# USB_PROGRAMER.net
KiCad netlist of a schematic drawn in Altium Designer
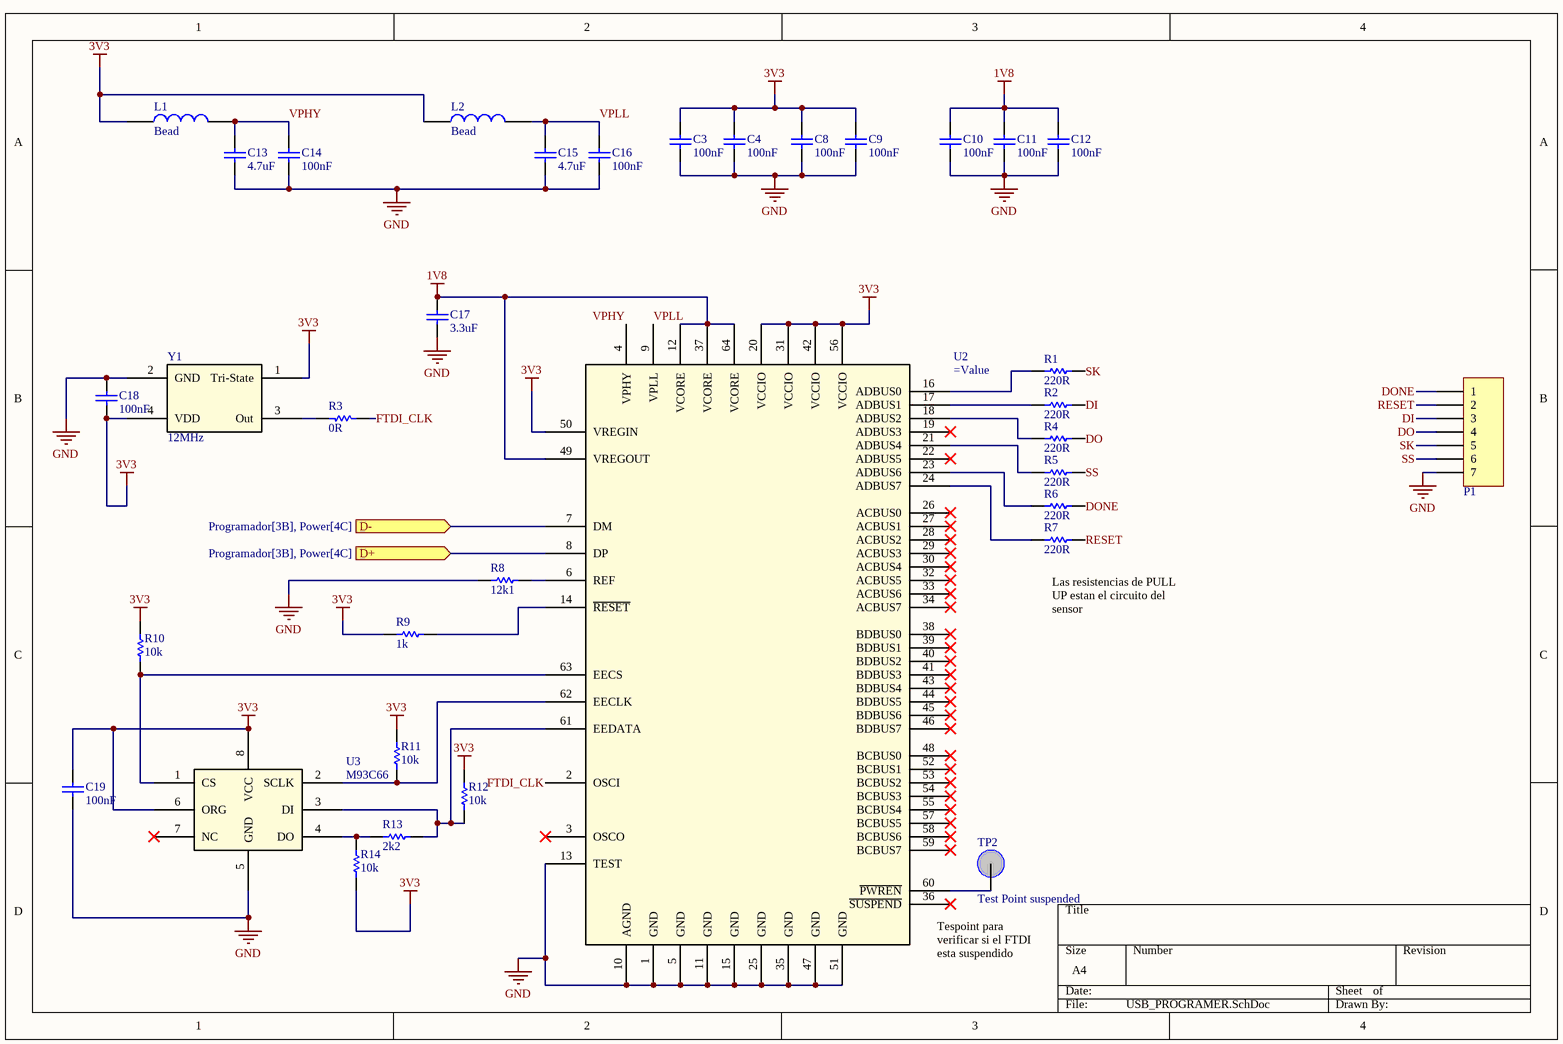
[diagram p0: USB_PROGRAMER.SchDoc]

(export (version "E")
  (design (tool "Eeschema 10.0.6"))
  (components
    (comp (ref "C3")
      (value "100nF")
      (footprint "C_0805_2013_b")
      (description "Capacitor SMD 0805")
      (fields (field (name "TOLERANCE") "10%") (field (name "VOLTAGE") "50V"))
      (libsource (lib "MyLibraryV2") (part "C_100nF_50V_b"))
    )
    (comp (ref "C4")
      (value "100nF")
      (footprint "C_0805_2013_b")
      (description "Capacitor SMD 0805")
      (fields (field (name "TOLERANCE") "10%") (field (name "VOLTAGE") "50V"))
      (libsource (lib "MyLibraryV2") (part "C_100nF_50V_b"))
    )
    (comp (ref "C8")
      (value "100nF")
      (footprint "C_0805_2013_b")
      (description "Capacitor SMD 0805")
      (fields (field (name "TOLERANCE") "10%") (field (name "VOLTAGE") "50V"))
      (libsource (lib "MyLibraryV2") (part "C_100nF_50V_b"))
    )
    (comp (ref "C9")
      (value "100nF")
      (footprint "C_0805_2013_b")
      (description "Capacitor SMD 0805")
      (fields (field (name "TOLERANCE") "10%") (field (name "VOLTAGE") "50V"))
      (libsource (lib "MyLibraryV2") (part "C_100nF_50V_b"))
    )
    (comp (ref "C10")
      (value "100nF")
      (footprint "C_0805_2013_b")
      (description "Capacitor SMD 0805")
      (fields (field (name "TOLERANCE") "10%") (field (name "VOLTAGE") "50V"))
      (libsource (lib "MyLibraryV2") (part "C_100nF_50V_b"))
    )
    (comp (ref "C11")
      (value "100nF")
      (footprint "C_0805_2013_b")
      (description "Capacitor SMD 0805")
      (fields (field (name "TOLERANCE") "10%") (field (name "VOLTAGE") "50V"))
      (libsource (lib "MyLibraryV2") (part "C_100nF_50V_b"))
    )
    (comp (ref "C12")
      (value "100nF")
      (footprint "C_0805_2013_b")
      (description "Capacitor SMD 0805")
      (fields (field (name "TOLERANCE") "10%") (field (name "VOLTAGE") "50V"))
      (libsource (lib "MyLibraryV2") (part "C_100nF_50V_b"))
    )
    (comp (ref "C13")
      (value "4.7uF")
      (footprint "C_0805_2013_b")
      (description "(Modificar) Capacitor SMD 0805")
      (libsource (lib "MyLibraryV2") (part "C_4.7uF_10V_b"))
    )
    (comp (ref "C14")
      (value "100nF")
      (footprint "C_0805_2013_b")
      (description "Capacitor SMD 0805")
      (fields (field (name "TOLERANCE") "10%") (field (name "VOLTAGE") "50V"))
      (libsource (lib "MyLibraryV2") (part "C_100nF_50V_b"))
    )
    (comp (ref "C15")
      (value "4.7uF")
      (footprint "C_0805_2013_b")
      (description "(Modificar) Capacitor SMD 0805")
      (libsource (lib "MyLibraryV2") (part "C_4.7uF_10V_b"))
    )
    (comp (ref "C16")
      (value "100nF")
      (footprint "C_0805_2013_b")
      (description "Capacitor SMD 0805")
      (fields (field (name "TOLERANCE") "10%") (field (name "VOLTAGE") "50V"))
      (libsource (lib "MyLibraryV2") (part "C_100nF_50V_b"))
    )
    (comp (ref "C17")
      (value "3.3uF")
      (footprint "C_0805_2013_b")
      (description "(Generico) Capacitor SMD 0805")
      (libsource (lib "MyLibraryV2") (part "C_?F_?_b"))
    )
    (comp (ref "C18")
      (value "100nF")
      (footprint "C_0805_2013_b")
      (description "Capacitor SMD 0805")
      (fields (field (name "TOLERANCE") "10%") (field (name "VOLTAGE") "50V"))
      (libsource (lib "MyLibraryV2") (part "C_100nF_50V_b"))
    )
    (comp (ref "C19")
      (value "100nF")
      (footprint "C_0805_2013_b")
      (description "Capacitor SMD 0805")
      (fields (field (name "TOLERANCE") "10%") (field (name "VOLTAGE") "50V"))
      (libsource (lib "MyLibraryV2") (part "C_100nF_50V_b"))
    )
    (comp (ref "L1")
      (value "Bead")
      (footprint "L_0805_2013")
      (description "Inductor SMD 0805")
      (fields
        (field (name "MANUFACTURER") "Pulse")
        (field (name "MANUFACTURER PART NUMBER") "PE-0805PFB600ST")
      )
      (libsource (lib "MyLibraryV2") (part "L_Bead"))
    )
    (comp (ref "L2")
      (value "Bead")
      (footprint "L_0805_2013")
      (description "Inductor SMD 0805")
      (fields
        (field (name "MANUFACTURER") "Pulse")
        (field (name "MANUFACTURER PART NUMBER") "PE-0805PFB600ST")
      )
      (libsource (lib "MyLibraryV2") (part "L_Bead"))
    )
    (comp (ref "P1")
      (value "BORNERA 6 ENCH")
      (footprint "P_CON1X7")
      (description "Bornera 7")
      (libsource (lib "MyLibraryV2") (part "P_BORNERA 7"))
    )
    (comp (ref "R1")
      (value "220R")
      (footprint "R_0805_2012_a")
      (description "Resistor SMD 0805")
      (fields (field (name "TOLERANCE") "1%") (field (name "MANUFACTURER") "Bourns"))
      (libsource (lib "MyLibraryV2") (part "R_220R_b"))
    )
    (comp (ref "R2")
      (value "220R")
      (footprint "R_0805_2012_a")
      (description "Resistor SMD 0805")
      (fields (field (name "TOLERANCE") "1%") (field (name "MANUFACTURER") "Bourns"))
      (libsource (lib "MyLibraryV2") (part "R_220R_b"))
    )
    (comp (ref "R3")
      (value "0R")
      (footprint "R_0805_2012_a")
      (description "Resistor SMD 0805")
      (fields
        (field (name "MANUFACTURER") "Stackpole Electronics")
        (field (name "MANUFACTURER PART NUMBER") "RMCF0805ZT0R00")
      )
      (libsource (lib "MyLibraryV2") (part "R_0R_b"))
    )
    (comp (ref "R4")
      (value "220R")
      (footprint "R_0805_2012_a")
      (description "Resistor SMD 0805")
      (fields (field (name "TOLERANCE") "1%") (field (name "MANUFACTURER") "Bourns"))
      (libsource (lib "MyLibraryV2") (part "R_220R_b"))
    )
    (comp (ref "R5")
      (value "220R")
      (footprint "R_0805_2012_a")
      (description "Resistor SMD 0805")
      (fields (field (name "TOLERANCE") "1%") (field (name "MANUFACTURER") "Bourns"))
      (libsource (lib "MyLibraryV2") (part "R_220R_b"))
    )
    (comp (ref "R6")
      (value "220R")
      (footprint "R_0805_2012_a")
      (description "Resistor SMD 0805")
      (fields (field (name "TOLERANCE") "1%") (field (name "MANUFACTURER") "Bourns"))
      (libsource (lib "MyLibraryV2") (part "R_220R_b"))
    )
    (comp (ref "R7")
      (value "220R")
      (footprint "R_0805_2012_a")
      (description "Resistor SMD 0805")
      (fields (field (name "TOLERANCE") "1%") (field (name "MANUFACTURER") "Bourns"))
      (libsource (lib "MyLibraryV2") (part "R_220R_b"))
    )
    (comp (ref "R8")
      (value "12k1")
      (footprint "R_0805_2012_a")
      (description "Resistor SMD 0805")
      (fields (field (name "TOLERANCE") "1%") (field (name "MANUFACTURER") "Stackpole Electronics"))
      (libsource (lib "MyLibraryV2") (part "R_12k1_b"))
    )
    (comp (ref "R9")
      (value "1k")
      (footprint "R_0805_2012_a")
      (description "Resistor SMD 0805")
      (fields (field (name "TOLERANCE") "1%") (field (name "MANUFACTURER") "Bourns"))
      (libsource (lib "MyLibraryV2") (part "R_1k_b"))
    )
    (comp (ref "R10")
      (value "10k")
      (footprint "R_0805_2012_a")
      (description "Resistor SMD 0805")
      (fields (field (name "TOLERANCE") "1%") (field (name "MANUFACTURER") "Yageo"))
      (libsource (lib "MyLibraryV2") (part "R_10k_b"))
    )
    (comp (ref "R11")
      (value "10k")
      (footprint "R_0805_2012_a")
      (description "Resistor SMD 0805")
      (fields (field (name "TOLERANCE") "1%") (field (name "MANUFACTURER") "Yageo"))
      (libsource (lib "MyLibraryV2") (part "R_10k_b"))
    )
    (comp (ref "R12")
      (value "10k")
      (footprint "R_0805_2012_a")
      (description "Resistor SMD 0805")
      (fields (field (name "TOLERANCE") "1%") (field (name "MANUFACTURER") "Yageo"))
      (libsource (lib "MyLibraryV2") (part "R_10k_b"))
    )
    (comp (ref "R13")
      (value "2k2")
      (footprint "R_0805_2012_a")
      (description "Resistor SMD 0805")
      (fields (field (name "TOLERANCE") "1%") (field (name "MANUFACTURER") "Bourns"))
      (libsource (lib "MyLibraryV2") (part "R_2k2_b"))
    )
    (comp (ref "R14")
      (value "10k")
      (footprint "R_0805_2012_a")
      (description "Resistor SMD 0805")
      (fields (field (name "TOLERANCE") "1%") (field (name "MANUFACTURER") "Yageo"))
      (libsource (lib "MyLibraryV2") (part "R_10k_b"))
    )
    (comp (ref "TP2")
      (value "Test Point suspended")
      (footprint "TP SMD")
      (description "Test Point SMD")
      (fields (field (name "PUBLISHER") "Altium Limited"))
      (libsource (lib "MyLibraryV2") (part "P_T_TP"))
    )
    (comp (ref "U2") (value "~") (footprint "U_TQFP-64") (libsource (lib "Mi_lib") (part "U_FT2232H")))
    (comp (ref "U3") (value "M93C66") (footprint "U_SO-8") (libsource (lib "Mi_lib") (part "U_M93C66")))
    (comp (ref "Y1")
      (value "12MHz")
      (footprint "Y_SMD-XTAL-12MHz")
      (libsource (lib "Mi_lib") (part "Y_12MHZ"))
    )
  )
  (nets
    (net (code "1") (name "/D+") (class "Default")
      (node (ref "U2") (pin "8") (pinfunction "DP_8") (pintype "passive"))
    )
    (net (code "2") (name "/D-") (class "Default")
      (node (ref "U2") (pin "7") (pinfunction "DM_7") (pintype "passive"))
    )
    (net (code "3") (name "/DI") (class "Default")
      (node (ref "P1") (pin "3") (pinfunction "3_3") (pintype "passive"))
      (node (ref "R2") (pin "2") (pinfunction "2_2") (pintype "passive"))
    )
    (net (code "4") (name "/DO") (class "Default")
      (node (ref "P1") (pin "4") (pinfunction "4_4") (pintype "passive"))
      (node (ref "R4") (pin "2") (pinfunction "2_2") (pintype "passive"))
    )
    (net (code "5") (name "/DONE") (class "Default")
      (node (ref "P1") (pin "1") (pinfunction "1_1") (pintype "passive"))
      (node (ref "R6") (pin "2") (pinfunction "2_2") (pintype "passive"))
    )
    (net (code "6") (name "/FTDI_CLK") (class "Default")
      (node (ref "R3") (pin "1") (pinfunction "1_1") (pintype "passive"))
      (node (ref "U2") (pin "2") (pinfunction "OSCI_2") (pintype "passive"))
    )
    (net (code "7") (name "/RESET") (class "Default")
      (node (ref "P1") (pin "2") (pinfunction "2_2") (pintype "passive"))
      (node (ref "R7") (pin "2") (pinfunction "2_2") (pintype "passive"))
    )
    (net (code "8") (name "/SK") (class "Default")
      (node (ref "P1") (pin "5") (pinfunction "5_5") (pintype "passive"))
      (node (ref "R1") (pin "2") (pinfunction "2_2") (pintype "passive"))
    )
    (net (code "9") (name "/SS") (class "Default")
      (node (ref "P1") (pin "6") (pinfunction "6_6") (pintype "passive"))
      (node (ref "R5") (pin "2") (pinfunction "2_2") (pintype "passive"))
    )
    (net (code "10") (name "/VPHY") (class "Default")
      (node (ref "C13") (pin "2") (pinfunction "2_2") (pintype "passive"))
      (node (ref "C14") (pin "2") (pinfunction "2_2") (pintype "passive"))
      (node (ref "L1") (pin "2") (pinfunction "2_2") (pintype "passive"))
      (node (ref "U2") (pin "4") (pinfunction "VPHY_4") (pintype "passive"))
    )
    (net (code "11") (name "/VPLL") (class "Default")
      (node (ref "C15") (pin "2") (pinfunction "2_2") (pintype "passive"))
      (node (ref "C16") (pin "2") (pinfunction "2_2") (pintype "passive"))
      (node (ref "L2") (pin "2") (pinfunction "2_2") (pintype "passive"))
      (node (ref "U2") (pin "9") (pinfunction "VPLL_9") (pintype "passive"))
    )
    (net (code "12") (name "1V8") (class "Default")
      (node (ref "C10") (pin "2") (pinfunction "2_2") (pintype "passive"))
      (node (ref "C11") (pin "2") (pinfunction "2_2") (pintype "passive"))
      (node (ref "C12") (pin "2") (pinfunction "2_2") (pintype "passive"))
      (node (ref "C17") (pin "2") (pinfunction "2_2") (pintype "passive"))
      (node (ref "U2") (pin "12") (pinfunction "VCORE_12") (pintype "passive"))
      (node (ref "U2") (pin "37") (pinfunction "VCORE_37") (pintype "passive"))
      (node (ref "U2") (pin "49") (pinfunction "VREGOUT_49") (pintype "passive"))
      (node (ref "U2") (pin "64") (pinfunction "VCORE_64") (pintype "passive"))
    )
    (net (code "13") (name "3V3") (class "Default")
      (node (ref "C18") (pin "1") (pinfunction "1_1") (pintype "passive"))
      (node (ref "C19") (pin "2") (pinfunction "2_2") (pintype "passive"))
      (node (ref "C3") (pin "2") (pinfunction "2_2") (pintype "passive"))
      (node (ref "C4") (pin "2") (pinfunction "2_2") (pintype "passive"))
      (node (ref "C8") (pin "2") (pinfunction "2_2") (pintype "passive"))
      (node (ref "C9") (pin "2") (pinfunction "2_2") (pintype "passive"))
      (node (ref "L1") (pin "1") (pinfunction "1_1") (pintype "passive"))
      (node (ref "L2") (pin "1") (pinfunction "1_1") (pintype "passive"))
      (node (ref "R10") (pin "2") (pinfunction "2_2") (pintype "passive"))
      (node (ref "R11") (pin "2") (pinfunction "2_2") (pintype "passive"))
      (node (ref "R12") (pin "2") (pinfunction "2_2") (pintype "passive"))
      (node (ref "R14") (pin "1") (pinfunction "1_1") (pintype "passive"))
      (node (ref "R9") (pin "1") (pinfunction "1_1") (pintype "passive"))
      (node (ref "U2") (pin "20") (pinfunction "VCCIO_20") (pintype "passive"))
      (node (ref "U2") (pin "31") (pinfunction "VCCIO_31") (pintype "passive"))
      (node (ref "U2") (pin "42") (pinfunction "VCCIO_42") (pintype "passive"))
      (node (ref "U2") (pin "50") (pinfunction "VREGIN_50") (pintype "passive"))
      (node (ref "U2") (pin "56") (pinfunction "VCCIO_56") (pintype "passive"))
      (node (ref "U3") (pin "6") (pinfunction "ORG_6") (pintype "passive"))
      (node (ref "U3") (pin "8") (pinfunction "VCC_8") (pintype "passive"))
      (node (ref "Y1") (pin "1") (pinfunction "Tri-State_1") (pintype "passive"))
      (node (ref "Y1") (pin "4") (pinfunction "VDD_4") (pintype "passive"))
    )
    (net (code "14") (name "GND") (class "Default")
      (node (ref "C10") (pin "1") (pinfunction "1_1") (pintype "passive"))
      (node (ref "C11") (pin "1") (pinfunction "1_1") (pintype "passive"))
      (node (ref "C12") (pin "1") (pinfunction "1_1") (pintype "passive"))
      (node (ref "C13") (pin "1") (pinfunction "1_1") (pintype "passive"))
      (node (ref "C14") (pin "1") (pinfunction "1_1") (pintype "passive"))
      (node (ref "C15") (pin "1") (pinfunction "1_1") (pintype "passive"))
      (node (ref "C16") (pin "1") (pinfunction "1_1") (pintype "passive"))
      (node (ref "C17") (pin "1") (pinfunction "1_1") (pintype "passive"))
      (node (ref "C18") (pin "2") (pinfunction "2_2") (pintype "passive"))
      (node (ref "C19") (pin "1") (pinfunction "1_1") (pintype "passive"))
      (node (ref "C3") (pin "1") (pinfunction "1_1") (pintype "passive"))
      (node (ref "C4") (pin "1") (pinfunction "1_1") (pintype "passive"))
      (node (ref "C8") (pin "1") (pinfunction "1_1") (pintype "passive"))
      (node (ref "C9") (pin "1") (pinfunction "1_1") (pintype "passive"))
      (node (ref "P1") (pin "7") (pinfunction "7_7") (pintype "passive"))
      (node (ref "R8") (pin "1") (pinfunction "1_1") (pintype "passive"))
      (node (ref "U2") (pin "1") (pinfunction "GND_1") (pintype "passive"))
      (node (ref "U2") (pin "10") (pinfunction "AGND_10") (pintype "passive"))
      (node (ref "U2") (pin "11") (pinfunction "GND_11") (pintype "passive"))
      (node (ref "U2") (pin "13") (pinfunction "TEST_13") (pintype "passive"))
      (node (ref "U2") (pin "15") (pinfunction "GND_15") (pintype "passive"))
      (node (ref "U2") (pin "25") (pinfunction "GND_25") (pintype "passive"))
      (node (ref "U2") (pin "35") (pinfunction "GND_35") (pintype "passive"))
      (node (ref "U2") (pin "47") (pinfunction "GND_47") (pintype "passive"))
      (node (ref "U2") (pin "5") (pinfunction "GND_5") (pintype "passive"))
      (node (ref "U2") (pin "51") (pinfunction "GND_51") (pintype "passive"))
      (node (ref "U3") (pin "5") (pinfunction "GND_5") (pintype "passive"))
      (node (ref "Y1") (pin "2") (pinfunction "GND_2") (pintype "passive"))
    )
    (net (code "15") (name "Net-(U2-ADBUS0)") (class "Default")
      (node (ref "R1") (pin "1") (pinfunction "1_1") (pintype "passive"))
      (node (ref "U2") (pin "16") (pinfunction "ADBUS0_16") (pintype "passive"))
    )
    (net (code "16") (name "Net-(U2-ADBUS1)") (class "Default")
      (node (ref "R2") (pin "1") (pinfunction "1_1") (pintype "passive"))
      (node (ref "U2") (pin "17") (pinfunction "ADBUS1_17") (pintype "passive"))
    )
    (net (code "17") (name "Net-(U2-ADBUS2)") (class "Default")
      (node (ref "R4") (pin "1") (pinfunction "1_1") (pintype "passive"))
      (node (ref "U2") (pin "18") (pinfunction "ADBUS2_18") (pintype "passive"))
    )
    (net (code "18") (name "Net-(U2-ADBUS4)") (class "Default")
      (node (ref "R5") (pin "1") (pinfunction "1_1") (pintype "passive"))
      (node (ref "U2") (pin "21") (pinfunction "ADBUS4_21") (pintype "passive"))
    )
    (net (code "19") (name "Net-(U2-ADBUS6)") (class "Default")
      (node (ref "R6") (pin "1") (pinfunction "1_1") (pintype "passive"))
      (node (ref "U2") (pin "23") (pinfunction "ADBUS6_23") (pintype "passive"))
    )
    (net (code "20") (name "Net-(U2-ADBUS7)") (class "Default")
      (node (ref "R7") (pin "1") (pinfunction "1_1") (pintype "passive"))
      (node (ref "U2") (pin "24") (pinfunction "ADBUS7_24") (pintype "passive"))
    )
    (net (code "21") (name "Net-(U2-EECLK)") (class "Default")
      (node (ref "R11") (pin "1") (pinfunction "1_1") (pintype "passive"))
      (node (ref "U2") (pin "62") (pinfunction "EECLK_62") (pintype "passive"))
      (node (ref "U3") (pin "2") (pinfunction "SCLK_2") (pintype "passive"))
    )
    (net (code "22") (name "Net-(U2-EECS)") (class "Default")
      (node (ref "R10") (pin "1") (pinfunction "1_1") (pintype "passive"))
      (node (ref "U2") (pin "63") (pinfunction "EECS_63") (pintype "passive"))
      (node (ref "U3") (pin "1") (pinfunction "CS_1") (pintype "passive"))
    )
    (net (code "23") (name "Net-(U2-EEDATA)") (class "Default")
      (node (ref "R12") (pin "1") (pinfunction "1_1") (pintype "passive"))
      (node (ref "R13") (pin "2") (pinfunction "2_2") (pintype "passive"))
      (node (ref "U2") (pin "61") (pinfunction "EEDATA_61") (pintype "passive"))
      (node (ref "U3") (pin "3") (pinfunction "DI_3") (pintype "passive"))
    )
    (net (code "24") (name "Net-(U2-REF)") (class "Default")
      (node (ref "R8") (pin "2") (pinfunction "2_2") (pintype "passive"))
      (node (ref "U2") (pin "6") (pinfunction "REF_6") (pintype "passive"))
    )
    (net (code "25") (name "Net-(U2-~{PWREN})") (class "Default")
      (node (ref "TP2") (pin "1") (pinfunction "1_1") (pintype "passive"))
      (node (ref "U2") (pin "60") (pinfunction "~{PWREN}_60") (pintype "passive"))
    )
    (net (code "26") (name "Net-(U2-~{RESET})") (class "Default")
      (node (ref "R9") (pin "2") (pinfunction "2_2") (pintype "passive"))
      (node (ref "U2") (pin "14") (pinfunction "~{RESET}_14") (pintype "passive"))
    )
    (net (code "27") (name "Net-(U3-DO)") (class "Default")
      (node (ref "R13") (pin "1") (pinfunction "1_1") (pintype "passive"))
      (node (ref "R14") (pin "2") (pinfunction "2_2") (pintype "passive"))
      (node (ref "U3") (pin "4") (pinfunction "DO_4") (pintype "passive"))
    )
    (net (code "28") (name "Net-(Y1-Out)") (class "Default")
      (node (ref "R3") (pin "2") (pinfunction "2_2") (pintype "passive"))
      (node (ref "Y1") (pin "3") (pinfunction "Out_3") (pintype "passive"))
    )
    (net (code "29") (name "unconnected-(U2-ACBUS0-Pad26)") (class "Default")
      (node (ref "U2") (pin "26") (pinfunction "ACBUS0_26") (pintype "passive+no_connect"))
    )
    (net (code "30") (name "unconnected-(U2-ACBUS1-Pad27)") (class "Default")
      (node (ref "U2") (pin "27") (pinfunction "ACBUS1_27") (pintype "passive+no_connect"))
    )
    (net (code "31") (name "unconnected-(U2-ACBUS2-Pad28)") (class "Default")
      (node (ref "U2") (pin "28") (pinfunction "ACBUS2_28") (pintype "passive+no_connect"))
    )
    (net (code "32") (name "unconnected-(U2-ACBUS3-Pad29)") (class "Default")
      (node (ref "U2") (pin "29") (pinfunction "ACBUS3_29") (pintype "passive+no_connect"))
    )
    (net (code "33") (name "unconnected-(U2-ACBUS4-Pad30)") (class "Default")
      (node (ref "U2") (pin "30") (pinfunction "ACBUS4_30") (pintype "passive+no_connect"))
    )
    (net (code "34") (name "unconnected-(U2-ACBUS5-Pad32)") (class "Default")
      (node (ref "U2") (pin "32") (pinfunction "ACBUS5_32") (pintype "passive+no_connect"))
    )
    (net (code "35") (name "unconnected-(U2-ACBUS6-Pad33)") (class "Default")
      (node (ref "U2") (pin "33") (pinfunction "ACBUS6_33") (pintype "passive+no_connect"))
    )
    (net (code "36") (name "unconnected-(U2-ACBUS7-Pad34)") (class "Default")
      (node (ref "U2") (pin "34") (pinfunction "ACBUS7_34") (pintype "passive+no_connect"))
    )
    (net (code "37") (name "unconnected-(U2-ADBUS3-Pad19)") (class "Default")
      (node (ref "U2") (pin "19") (pinfunction "ADBUS3_19") (pintype "passive+no_connect"))
    )
    (net (code "38") (name "unconnected-(U2-ADBUS5-Pad22)") (class "Default")
      (node (ref "U2") (pin "22") (pinfunction "ADBUS5_22") (pintype "passive+no_connect"))
    )
    (net (code "39") (name "unconnected-(U2-BCBUS0-Pad48)") (class "Default")
      (node (ref "U2") (pin "48") (pinfunction "BCBUS0_48") (pintype "passive+no_connect"))
    )
    (net (code "40") (name "unconnected-(U2-BCBUS1-Pad52)") (class "Default")
      (node (ref "U2") (pin "52") (pinfunction "BCBUS1_52") (pintype "passive+no_connect"))
    )
    (net (code "41") (name "unconnected-(U2-BCBUS2-Pad53)") (class "Default")
      (node (ref "U2") (pin "53") (pinfunction "BCBUS2_53") (pintype "passive+no_connect"))
    )
    (net (code "42") (name "unconnected-(U2-BCBUS3-Pad54)") (class "Default")
      (node (ref "U2") (pin "54") (pinfunction "BCBUS3_54") (pintype "passive+no_connect"))
    )
    (net (code "43") (name "unconnected-(U2-BCBUS4-Pad55)") (class "Default")
      (node (ref "U2") (pin "55") (pinfunction "BCBUS4_55") (pintype "passive+no_connect"))
    )
    (net (code "44") (name "unconnected-(U2-BCBUS5-Pad57)") (class "Default")
      (node (ref "U2") (pin "57") (pinfunction "BCBUS5_57") (pintype "passive+no_connect"))
    )
    (net (code "45") (name "unconnected-(U2-BCBUS6-Pad58)") (class "Default")
      (node (ref "U2") (pin "58") (pinfunction "BCBUS6_58") (pintype "passive+no_connect"))
    )
    (net (code "46") (name "unconnected-(U2-BCBUS7-Pad59)") (class "Default")
      (node (ref "U2") (pin "59") (pinfunction "BCBUS7_59") (pintype "passive+no_connect"))
    )
    (net (code "47") (name "unconnected-(U2-BDBUS0-Pad38)") (class "Default")
      (node (ref "U2") (pin "38") (pinfunction "BDBUS0_38") (pintype "passive+no_connect"))
    )
    (net (code "48") (name "unconnected-(U2-BDBUS1-Pad39)") (class "Default")
      (node (ref "U2") (pin "39") (pinfunction "BDBUS1_39") (pintype "passive+no_connect"))
    )
    (net (code "49") (name "unconnected-(U2-BDBUS2-Pad40)") (class "Default")
      (node (ref "U2") (pin "40") (pinfunction "BDBUS2_40") (pintype "passive+no_connect"))
    )
    (net (code "50") (name "unconnected-(U2-BDBUS3-Pad41)") (class "Default")
      (node (ref "U2") (pin "41") (pinfunction "BDBUS3_41") (pintype "passive+no_connect"))
    )
    (net (code "51") (name "unconnected-(U2-BDBUS4-Pad43)") (class "Default")
      (node (ref "U2") (pin "43") (pinfunction "BDBUS4_43") (pintype "passive+no_connect"))
    )
    (net (code "52") (name "unconnected-(U2-BDBUS5-Pad44)") (class "Default")
      (node (ref "U2") (pin "44") (pinfunction "BDBUS5_44") (pintype "passive+no_connect"))
    )
    (net (code "53") (name "unconnected-(U2-BDBUS6-Pad45)") (class "Default")
      (node (ref "U2") (pin "45") (pinfunction "BDBUS6_45") (pintype "passive+no_connect"))
    )
    (net (code "54") (name "unconnected-(U2-BDBUS7-Pad46)") (class "Default")
      (node (ref "U2") (pin "46") (pinfunction "BDBUS7_46") (pintype "passive+no_connect"))
    )
    (net (code "55") (name "unconnected-(U2-OSCO-Pad3)") (class "Default")
      (node (ref "U2") (pin "3") (pinfunction "OSCO_3") (pintype "passive+no_connect"))
    )
    (net (code "56") (name "unconnected-(U2-~{SUSPEND}-Pad36)") (class "Default")
      (node (ref "U2") (pin "36") (pinfunction "~{SUSPEND}_36") (pintype "passive+no_connect"))
    )
    (net (code "57") (name "unconnected-(U3-NC-Pad7)") (class "Default")
      (node (ref "U3") (pin "7") (pinfunction "NC_7") (pintype "passive+no_connect"))
    )
  )
)
